# HT32F12364.net
KiCad netlist of a schematic drawn in Altium Designer
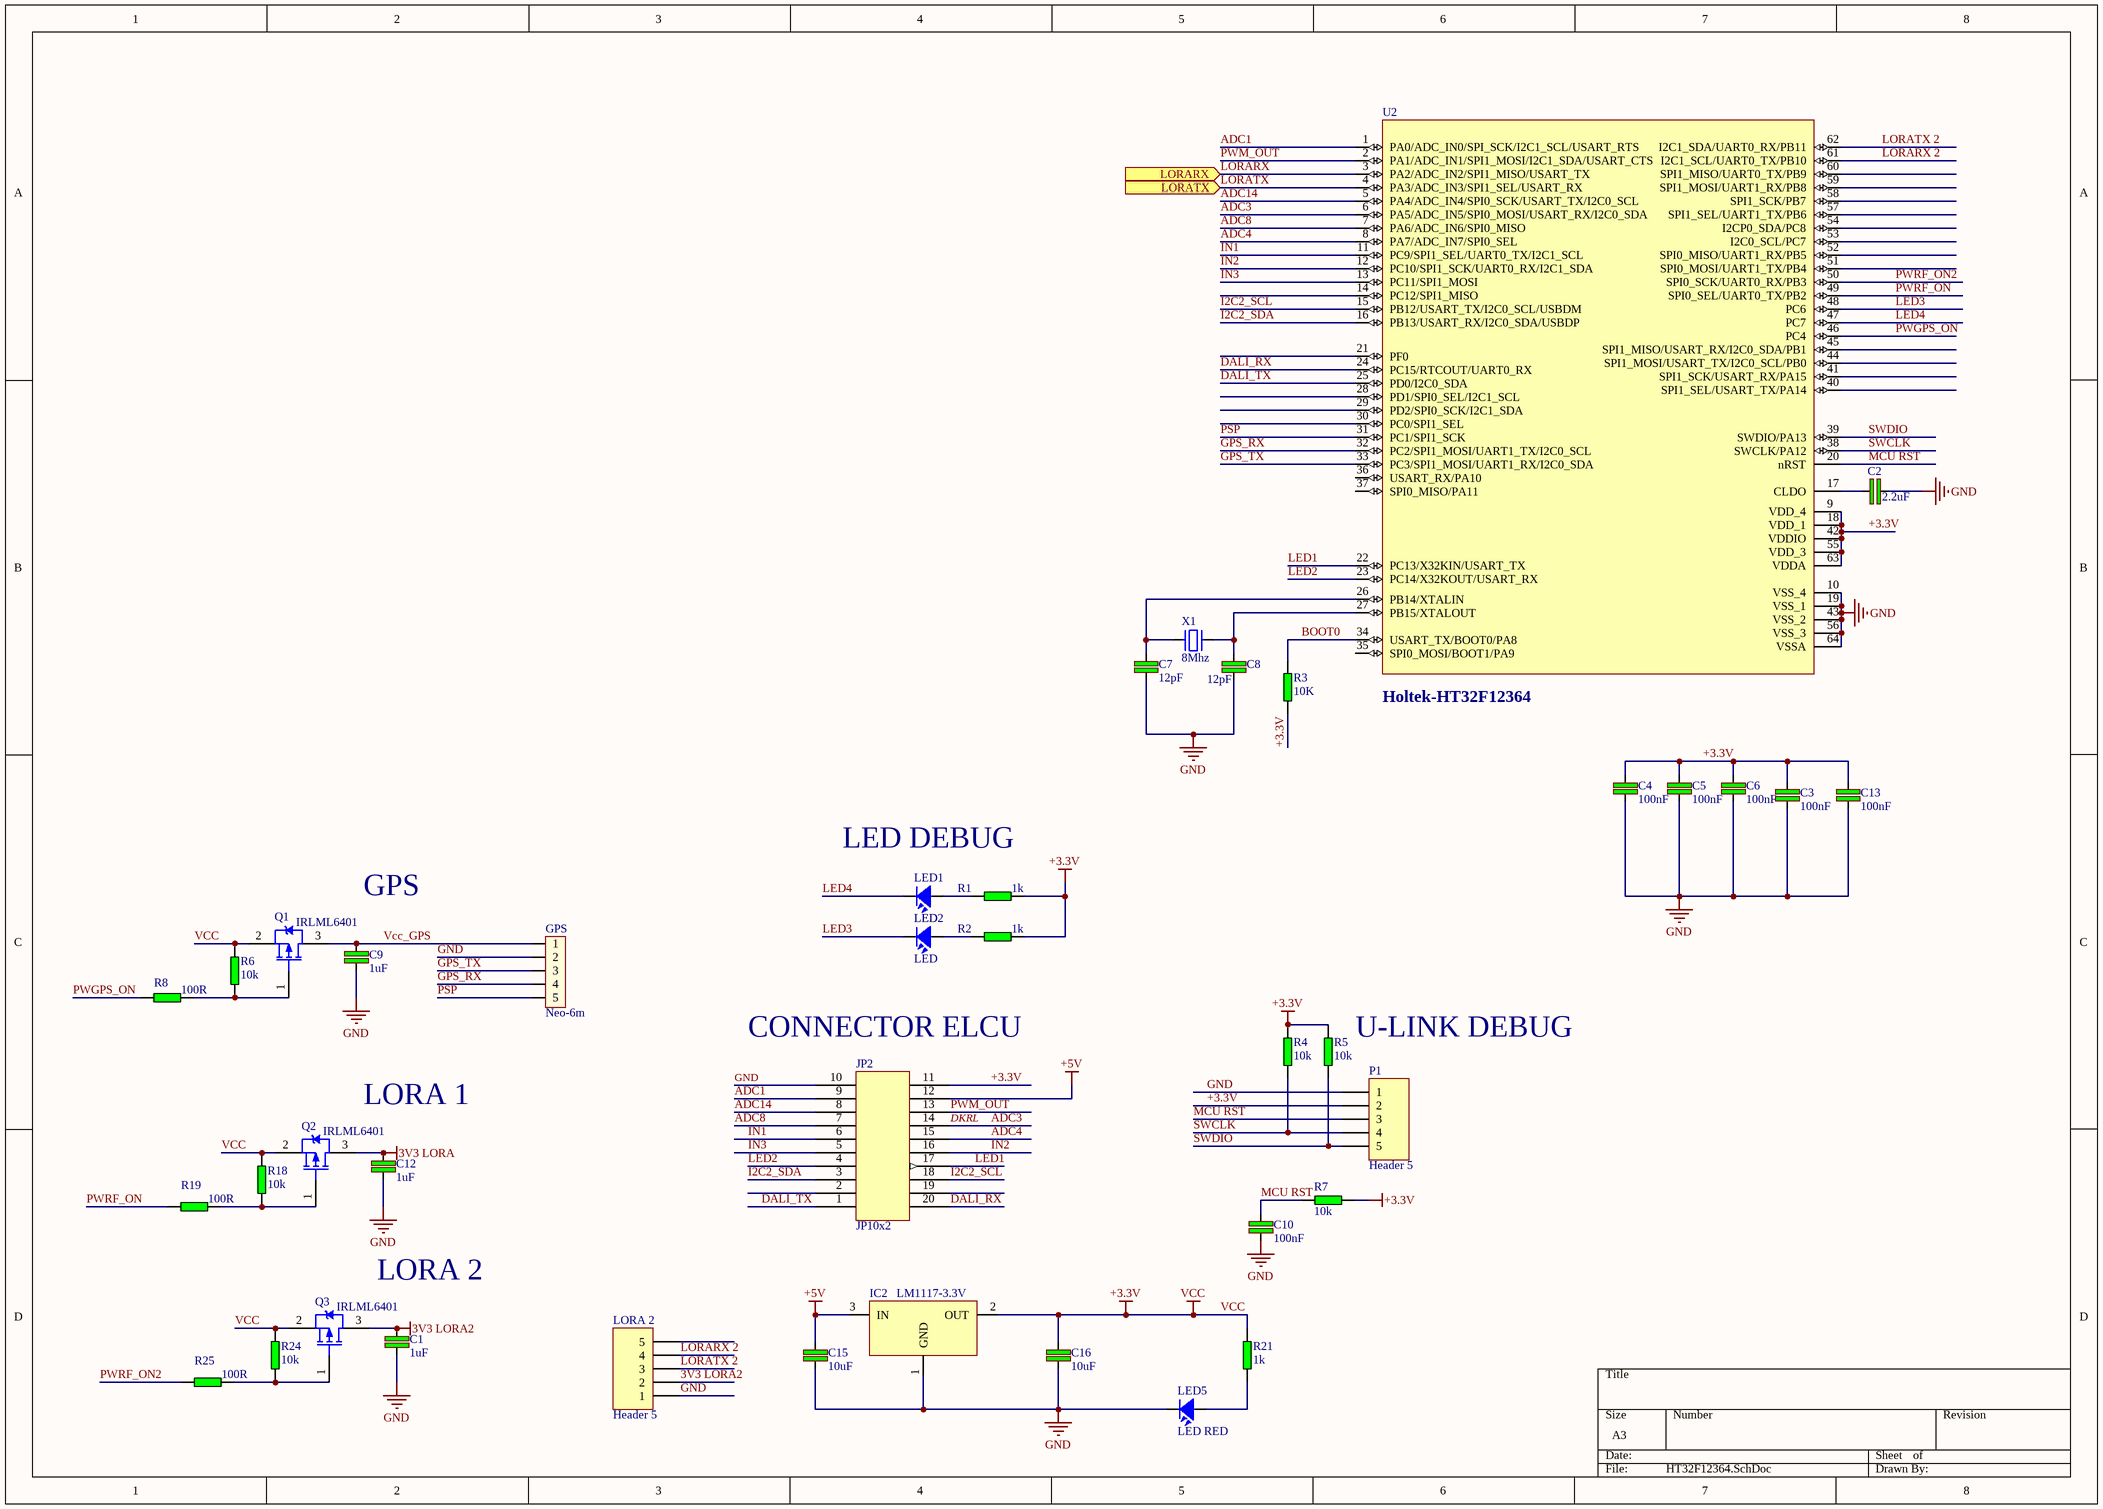
[diagram p0: HT32F12364.SchDoc]

(export (version "E")
  (design (tool "Eeschema 10.0.6"))
  (components
    (comp (ref "C1")
      (value "1uF")
      (footprint "C-0603")
      (description "Cap SMD")
      (libsource (lib "") (part "C_1"))
    )
    (comp (ref "C2")
      (value "2.2uF")
      (footprint "C-0603")
      (description "Cap SMD")
      (libsource (lib "") (part "C_2"))
    )
    (comp (ref "C3")
      (value "100nF")
      (footprint "C-0603")
      (description "Cap SMD")
      (libsource (lib "") (part "C_1"))
    )
    (comp (ref "C4")
      (value "100nF")
      (footprint "C-0603")
      (description "Cap SMD")
      (libsource (lib "") (part "C_1"))
    )
    (comp (ref "C5")
      (value "100nF")
      (footprint "C-0603")
      (description "Cap SMD")
      (libsource (lib "") (part "C_1"))
    )
    (comp (ref "C6")
      (value "100nF")
      (footprint "C-0603")
      (description "Cap SMD")
      (libsource (lib "") (part "C_1"))
    )
    (comp (ref "C7")
      (value "12pF")
      (footprint "C-0603")
      (description "Cap SMD")
      (libsource (lib "") (part "C_1"))
    )
    (comp (ref "C8")
      (value "12pF")
      (footprint "C-0603")
      (description "Cap SMD")
      (libsource (lib "") (part "C_1"))
    )
    (comp (ref "C9")
      (value "1uF")
      (footprint "C-0603")
      (description "Cap SMD")
      (libsource (lib "") (part "C_1"))
    )
    (comp (ref "C10")
      (value "100nF")
      (footprint "C-0603")
      (description "Cap SMD")
      (libsource (lib "Duy_Hai") (part "C"))
    )
    (comp (ref "C12")
      (value "1uF")
      (footprint "C-0603")
      (description "Cap SMD")
      (libsource (lib "") (part "C_1"))
    )
    (comp (ref "C13")
      (value "100nF")
      (footprint "C-0603")
      (description "Cap SMD")
      (libsource (lib "") (part "C_1"))
    )
    (comp (ref "C15")
      (value "10uF")
      (footprint "C-0805")
      (description "Cap np  1pF - 472pF")
      (libsource (lib "heromap") (part "CAP"))
    )
    (comp (ref "C16")
      (value "10uF")
      (footprint "C-0805")
      (description "Cap np  1pF - 472pF")
      (libsource (lib "heromap") (part "CAP"))
    )
    (comp (ref "GPS") (value "Neo-6m") (footprint "QUECTEL L80 MODULE") (libsource (lib "Cty1") (part "JP5")))
    (comp (ref "IC2")
      (value "LM1117-3.3V")
      (footprint "SOT223-4N")
      (fields (field (name "CREATOR") "Nguyen Ba Bien"))
      (libsource (lib "Cty1") (part "LM1117"))
    )
    (comp (ref "JP2")
      (value "JP10x2")
      (footprint "JP10-D2T")
      (description "Conector 10x2")
      (libsource (lib "Cty1") (part "CON10X2"))
    )
    (comp (ref "LED1")
      (value "LED")
      (footprint "LED-0805")
      (description "LED Single colour Green and Red")
      (libsource (lib "heromap") (part "LED"))
    )
    (comp (ref "LED2")
      (value "LED")
      (footprint "LED-0805")
      (description "LED Single colour Green and Red")
      (libsource (lib "heromap") (part "LED"))
    )
    (comp (ref "LED5")
      (value "LED RED")
      (footprint "LED-0805")
      (description "LED Single colour Green and Red")
      (libsource (lib "heromap") (part "LED"))
    )
    (comp (ref "LORA 2")
      (value "Header 5")
      (footprint "RAK3172 MODULE 2")
      (description "Header, 5-Pin")
      (fields (field (name "PUBLISHER") "Altium Limited"))
      (libsource (lib "heromap") (part "Header 5"))
    )
    (comp (ref "P1")
      (value "Header 5")
      (footprint "JP5")
      (description "Header, 5-Pin")
      (fields (field (name "PUBLISHER") "Altium Limited"))
      (libsource (lib "") (part "Header 5_1"))
    )
    (comp (ref "Q1")
      (value "IRLML6401")
      (footprint "Anh_Trung:SOT23")
      (description "HEXFET Power MOSFET")
      (fields (field (name "PUBLISHER") "Altium Limited"))
      (libsource (lib "IR Discrete MOSFET - Power") (part "IRLML6302"))
    )
    (comp (ref "Q2")
      (value "IRLML6401")
      (footprint "Anh_Trung:SOT23")
      (description "HEXFET Power MOSFET")
      (fields (field (name "PUBLISHER") "Altium Limited"))
      (libsource (lib "IR Discrete MOSFET - Power") (part "IRLML6302"))
    )
    (comp (ref "Q3")
      (value "IRLML6401")
      (footprint "Anh_Trung:SOT23")
      (description "HEXFET Power MOSFET")
      (fields (field (name "PUBLISHER") "Altium Limited"))
      (libsource (lib "IR Discrete MOSFET - Power") (part "IRLML6302"))
    )
    (comp (ref "R1")
      (value "1k")
      (footprint "R-0603")
      (description "Resistor 1/4W")
      (libsource (lib "") (part "RES_2"))
    )
    (comp (ref "R2")
      (value "1k")
      (footprint "R-0603")
      (description "Resistor 1/4W")
      (libsource (lib "") (part "RES_2"))
    )
    (comp (ref "R3")
      (value "10K")
      (footprint "R-0603")
      (description "Resistor 1/4W")
      (libsource (lib "Duy_Hai") (part "RES"))
    )
    (comp (ref "R4")
      (value "10k")
      (footprint "R-0603")
      (description "Resistor 1/4W")
      (libsource (lib "") (part "RES_1"))
    )
    (comp (ref "R5")
      (value "10k")
      (footprint "R-0603")
      (description "Resistor 1/4W")
      (libsource (lib "") (part "RES_1"))
    )
    (comp (ref "R6")
      (value "10k")
      (footprint "R-0603")
      (description "Resistor 1/4W")
      (libsource (lib "Duy_Hai") (part "RES"))
    )
    (comp (ref "R7")
      (value "10k")
      (footprint "R-0603")
      (description "Resistor 1/4W")
      (libsource (lib "") (part "RES_2"))
    )
    (comp (ref "R8")
      (value "100R")
      (footprint "R-0603")
      (description "Resistor 1/4W")
      (libsource (lib "") (part "RES_2"))
    )
    (comp (ref "R18")
      (value "10k")
      (footprint "R-0603")
      (description "Resistor 1/4W")
      (libsource (lib "Duy_Hai") (part "RES"))
    )
    (comp (ref "R19")
      (value "100R")
      (footprint "R-0603")
      (description "Resistor 1/4W")
      (libsource (lib "") (part "RES_2"))
    )
    (comp (ref "R21")
      (value "1k")
      (footprint "R-0603")
      (description "Resistor 1/4W")
      (libsource (lib "Duy_Hai") (part "RES"))
    )
    (comp (ref "R24")
      (value "10k")
      (footprint "R-0603")
      (description "Resistor 1/4W")
      (libsource (lib "Duy_Hai") (part "RES"))
    )
    (comp (ref "R25")
      (value "100R")
      (footprint "R-0603")
      (description "Resistor 1/4W")
      (libsource (lib "") (part "RES_2"))
    )
    (comp (ref "U2")
      (value "Holtek-HT32F12364")
      (footprint "LQFP-64PIN-7mmx7mm")
      (description "http://admin.epi-tech.com.vn//files/20210803/20210803162044_HT32F12364.pdf")
      (libsource (lib "ESP-07S") (part "Holtek-HT32F12364"))
    )
    (comp (ref "X1")
      (value "8Mhz")
      (footprint "XT2 - DAN - 5032")
      (description "Crystal For all Crystal 2pin.")
      (libsource (lib "Duy_Hai") (part "XT2"))
    )
  )
  (nets
    (net (code "1") (name "+3.3V") (class "Default")
      (node (ref "C13") (pin "1") (pinfunction "1_1") (pintype "passive"))
      (node (ref "C16") (pin "2") (pinfunction "2_2") (pintype "passive"))
      (node (ref "C3") (pin "1") (pinfunction "1_1") (pintype "passive"))
      (node (ref "C4") (pin "1") (pinfunction "1_1") (pintype "passive"))
      (node (ref "C5") (pin "1") (pinfunction "1_1") (pintype "passive"))
      (node (ref "C6") (pin "1") (pinfunction "1_1") (pintype "passive"))
      (node (ref "IC2") (pin "2") (pinfunction "OUT_2") (pintype "passive"))
      (node (ref "JP2") (pin "11") (pinfunction "13_11") (pintype "passive"))
      (node (ref "P1") (pin "2") (pinfunction "2_2") (pintype "passive"))
      (node (ref "Q1") (pin "2") (pinfunction "S_2") (pintype "passive"))
      (node (ref "Q2") (pin "2") (pinfunction "S_2") (pintype "passive"))
      (node (ref "Q3") (pin "2") (pinfunction "S_2") (pintype "passive"))
      (node (ref "R1") (pin "2") (pinfunction "2_2") (pintype "passive"))
      (node (ref "R18") (pin "2") (pinfunction "2_2") (pintype "passive"))
      (node (ref "R2") (pin "2") (pinfunction "2_2") (pintype "passive"))
      (node (ref "R21") (pin "2") (pinfunction "2_2") (pintype "passive"))
      (node (ref "R24") (pin "2") (pinfunction "2_2") (pintype "passive"))
      (node (ref "R3") (pin "1") (pinfunction "1_1") (pintype "passive"))
      (node (ref "R4") (pin "1") (pinfunction "1_1") (pintype "passive"))
      (node (ref "R5") (pin "1") (pinfunction "1_1") (pintype "passive"))
      (node (ref "R6") (pin "2") (pinfunction "2_2") (pintype "passive"))
      (node (ref "R7") (pin "2") (pinfunction "2_2") (pintype "passive"))
      (node (ref "U2") (pin "18") (pinfunction "VDD_1_18") (pintype "power_in"))
      (node (ref "U2") (pin "42") (pinfunction "VDDIO_42") (pintype "power_in"))
      (node (ref "U2") (pin "55") (pinfunction "VDD_3_55") (pintype "power_in"))
      (node (ref "U2") (pin "63") (pinfunction "VDDA_63") (pintype "power_in"))
      (node (ref "U2") (pin "9") (pinfunction "VDD_4_9") (pintype "power_in"))
    )
    (net (code "2") (name "+5V") (class "Default")
      (node (ref "C15") (pin "2") (pinfunction "2_2") (pintype "passive"))
      (node (ref "IC2") (pin "3") (pinfunction "IN_3") (pintype "passive"))
      (node (ref "JP2") (pin "12") (pinfunction "14_12") (pintype "passive"))
    )
    (net (code "3") (name "/ADC1") (class "Default")
      (node (ref "JP2") (pin "9") (pintype "passive"))
      (node (ref "U2") (pin "1") (pinfunction "PA0/ADC_IN0/SPI_SCK/I2C1_SCL/USART_RTS_1") (pintype "bidirectional"))
    )
    (net (code "4") (name "/ADC3") (class "Default")
      (node (ref "JP2") (pin "14") (pinfunction "16_14") (pintype "passive"))
      (node (ref "U2") (pin "6") (pinfunction "PA5/ADC_IN5/SPI0_MOSI/USART_RX/I2C0_SDA_6") (pintype "bidirectional"))
    )
    (net (code "5") (name "/ADC4") (class "Default")
      (node (ref "JP2") (pin "15") (pinfunction "17_15") (pintype "passive"))
      (node (ref "U2") (pin "8") (pinfunction "PA7/ADC_IN7/SPI0_SEL_8") (pintype "bidirectional"))
    )
    (net (code "6") (name "/ADC8") (class "Default")
      (node (ref "JP2") (pin "7") (pintype "passive"))
      (node (ref "U2") (pin "7") (pinfunction "PA6/ADC_IN6/SPI0_MISO_7") (pintype "bidirectional"))
    )
    (net (code "7") (name "/ADC14") (class "Default")
      (node (ref "JP2") (pin "8") (pintype "passive"))
      (node (ref "U2") (pin "5") (pinfunction "PA4/ADC_IN4/SPI0_SCK/USART_TX/I2C0_SCL_5") (pintype "bidirectional"))
    )
    (net (code "8") (name "/BOOT0") (class "Default")
      (node (ref "R3") (pin "2") (pinfunction "2_2") (pintype "passive"))
      (node (ref "U2") (pin "34") (pinfunction "USART_TX/BOOT0/PA8_34") (pintype "bidirectional"))
    )
    (net (code "9") (name "/DALI_RX") (class "Default")
      (node (ref "JP2") (pin "20") (pinfunction "22_20") (pintype "passive"))
      (node (ref "U2") (pin "24") (pinfunction "PC15/RTCOUT/UART0_RX_24") (pintype "bidirectional"))
    )
    (net (code "10") (name "/DALI_TX") (class "Default")
      (node (ref "JP2") (pin "1") (pintype "passive"))
      (node (ref "U2") (pin "25") (pinfunction "PD0/I2C0_SDA_25") (pintype "bidirectional"))
    )
    (net (code "11") (name "/GPS_RX") (class "Default")
      (node (ref "GPS") (pin "4") (pinfunction "4_4") (pintype "passive"))
      (node (ref "U2") (pin "32") (pinfunction "PC2/SPI1_MOSI/UART1_TX/I2C0_SCL_32") (pintype "bidirectional"))
    )
    (net (code "12") (name "/GPS_TX") (class "Default")
      (node (ref "GPS") (pin "3") (pinfunction "3_3") (pintype "passive"))
      (node (ref "U2") (pin "33") (pinfunction "PC3/SPI1_MOSI/UART1_RX/I2C0_SDA_33") (pintype "bidirectional"))
    )
    (net (code "13") (name "/I2C2_SCL") (class "Default")
      (node (ref "JP2") (pin "18") (pinfunction "20_18") (pintype "passive"))
      (node (ref "U2") (pin "15") (pinfunction "PB12/USART_TX/I2C0_SCL/USBDM_15") (pintype "bidirectional"))
    )
    (net (code "14") (name "/I2C2_SDA") (class "Default")
      (node (ref "JP2") (pin "3") (pintype "passive"))
      (node (ref "U2") (pin "16") (pinfunction "PB13/USART_RX/I2C0_SDA/USBDP_16") (pintype "bidirectional"))
    )
    (net (code "15") (name "/IN1") (class "Default")
      (node (ref "JP2") (pin "6") (pintype "passive"))
      (node (ref "U2") (pin "11") (pinfunction "PC9/SPI1_SEL/UART0_TX/I2C1_SCL_11") (pintype "bidirectional"))
    )
    (net (code "16") (name "/IN2") (class "Default")
      (node (ref "JP2") (pin "16") (pinfunction "18_16") (pintype "passive"))
      (node (ref "U2") (pin "12") (pinfunction "PC10/SPI1_SCK/UART0_RX/I2C1_SDA_12") (pintype "bidirectional"))
    )
    (net (code "17") (name "/IN3") (class "Default")
      (node (ref "JP2") (pin "5") (pintype "passive"))
      (node (ref "U2") (pin "13") (pinfunction "PC11/SPI1_MOSI_13") (pintype "bidirectional"))
    )
    (net (code "18") (name "/LED1") (class "Default")
      (node (ref "JP2") (pin "17") (pinfunction "19_17") (pintype "output"))
      (node (ref "U2") (pin "22") (pinfunction "PC13/X32KIN/USART_TX_22") (pintype "bidirectional"))
    )
    (net (code "19") (name "/LED2") (class "Default")
      (node (ref "JP2") (pin "4") (pintype "passive"))
      (node (ref "U2") (pin "23") (pinfunction "PC14/X32KOUT/USART_RX_23") (pintype "bidirectional"))
    )
    (net (code "20") (name "/LED3") (class "Default")
      (node (ref "LED2") (pin "2") (pinfunction "2_2") (pintype "passive"))
      (node (ref "U2") (pin "48") (pinfunction "PC6_48") (pintype "bidirectional"))
    )
    (net (code "21") (name "/LED4") (class "Default")
      (node (ref "LED1") (pin "2") (pinfunction "2_2") (pintype "passive"))
      (node (ref "U2") (pin "47") (pinfunction "PC7_47") (pintype "bidirectional"))
    )
    (net (code "22") (name "/LORARX") (class "Default")
      (node (ref "U2") (pin "3") (pinfunction "PA2/ADC_IN2/SPI1_MISO/USART_TX_3") (pintype "bidirectional"))
    )
    (net (code "23") (name "/LORARX 2") (class "Default")
      (node (ref "LORA 2") (pin "4") (pinfunction "4_4") (pintype "passive"))
      (node (ref "U2") (pin "61") (pinfunction "I2C1_SCL/UART0_TX/PB10_61") (pintype "bidirectional"))
    )
    (net (code "24") (name "/LORATX") (class "Default")
      (node (ref "U2") (pin "4") (pinfunction "PA3/ADC_IN3/SPI1_SEL/USART_RX_4") (pintype "bidirectional"))
    )
    (net (code "25") (name "/LORATX 2") (class "Default")
      (node (ref "LORA 2") (pin "3") (pinfunction "3_3") (pintype "passive"))
      (node (ref "U2") (pin "62") (pinfunction "I2C1_SDA/UART0_RX/PB11_62") (pintype "bidirectional"))
    )
    (net (code "26") (name "/MCU RST") (class "Default")
      (node (ref "C10") (pin "1") (pinfunction "1_1") (pintype "passive"))
      (node (ref "P1") (pin "3") (pinfunction "3_3") (pintype "passive"))
      (node (ref "R7") (pin "1") (pinfunction "1_1") (pintype "passive"))
      (node (ref "U2") (pin "20") (pinfunction "nRST_20") (pintype "passive"))
    )
    (net (code "27") (name "/PSP") (class "Default")
      (node (ref "GPS") (pin "5") (pinfunction "5_5") (pintype "passive"))
      (node (ref "U2") (pin "31") (pinfunction "PC1/SPI1_SCK_31") (pintype "bidirectional"))
    )
    (net (code "28") (name "/PWGPS_ON") (class "Default")
      (node (ref "R8") (pin "1") (pinfunction "1_1") (pintype "passive"))
      (node (ref "U2") (pin "46") (pinfunction "PC4_46") (pintype "bidirectional"))
    )
    (net (code "29") (name "/PWM_OUT") (class "Default")
      (node (ref "JP2") (pin "13") (pinfunction "15_13") (pintype "passive"))
      (node (ref "U2") (pin "2") (pinfunction "PA1/ADC_IN1/SPI1_MOSI/I2C1_SDA/USART_CTS_2") (pintype "bidirectional"))
    )
    (net (code "30") (name "/PWRF_ON") (class "Default")
      (node (ref "R19") (pin "1") (pinfunction "1_1") (pintype "passive"))
      (node (ref "U2") (pin "49") (pinfunction "SPI0_SEL/UART0_TX/PB2_49") (pintype "bidirectional"))
    )
    (net (code "31") (name "/PWRF_ON2") (class "Default")
      (node (ref "R25") (pin "1") (pinfunction "1_1") (pintype "passive"))
      (node (ref "U2") (pin "50") (pinfunction "SPI0_SCK/UART0_RX/PB3_50") (pintype "bidirectional"))
    )
    (net (code "32") (name "/SWCLK") (class "Default")
      (node (ref "P1") (pin "4") (pinfunction "4_4") (pintype "passive"))
      (node (ref "R4") (pin "2") (pinfunction "2_2") (pintype "passive"))
      (node (ref "U2") (pin "38") (pinfunction "SWCLK/PA12_38") (pintype "bidirectional"))
    )
    (net (code "33") (name "/SWDIO") (class "Default")
      (node (ref "P1") (pin "5") (pinfunction "5_5") (pintype "passive"))
      (node (ref "R5") (pin "2") (pinfunction "2_2") (pintype "passive"))
      (node (ref "U2") (pin "39") (pinfunction "SWDIO/PA13_39") (pintype "bidirectional"))
    )
    (net (code "34") (name "/Vcc_GPS") (class "Default")
      (node (ref "C9") (pin "1") (pinfunction "1_1") (pintype "passive"))
      (node (ref "GPS") (pin "1") (pinfunction "1_1") (pintype "passive"))
      (node (ref "Q1") (pin "3") (pinfunction "D_3") (pintype "passive"))
    )
    (net (code "35") (name "3V3 LORA") (class "Default")
      (node (ref "C12") (pin "1") (pinfunction "1_1") (pintype "passive"))
      (node (ref "Q2") (pin "3") (pinfunction "D_3") (pintype "passive"))
    )
    (net (code "36") (name "3V3 LORA2") (class "Default")
      (node (ref "C1") (pin "1") (pinfunction "1_1") (pintype "passive"))
      (node (ref "LORA 2") (pin "2") (pinfunction "2_2") (pintype "passive"))
      (node (ref "Q3") (pin "3") (pinfunction "D_3") (pintype "passive"))
    )
    (net (code "37") (name "GND") (class "Default")
      (node (ref "C1") (pin "2") (pinfunction "2_2") (pintype "passive"))
      (node (ref "C10") (pin "2") (pinfunction "2_2") (pintype "passive"))
      (node (ref "C12") (pin "2") (pinfunction "2_2") (pintype "passive"))
      (node (ref "C13") (pin "2") (pinfunction "2_2") (pintype "passive"))
      (node (ref "C15") (pin "1") (pinfunction "1_1") (pintype "passive"))
      (node (ref "C16") (pin "1") (pinfunction "1_1") (pintype "passive"))
      (node (ref "C2") (pin "2") (pinfunction "2_2") (pintype "passive"))
      (node (ref "C3") (pin "2") (pinfunction "2_2") (pintype "passive"))
      (node (ref "C4") (pin "2") (pinfunction "2_2") (pintype "passive"))
      (node (ref "C5") (pin "2") (pinfunction "2_2") (pintype "passive"))
      (node (ref "C6") (pin "2") (pinfunction "2_2") (pintype "passive"))
      (node (ref "C7") (pin "2") (pinfunction "2_2") (pintype "passive"))
      (node (ref "C8") (pin "2") (pinfunction "2_2") (pintype "passive"))
      (node (ref "C9") (pin "2") (pinfunction "2_2") (pintype "passive"))
      (node (ref "GPS") (pin "2") (pinfunction "2_2") (pintype "passive"))
      (node (ref "IC2") (pin "1") (pinfunction "GND_1") (pintype "passive"))
      (node (ref "JP2") (pin "10") (pintype "passive"))
      (node (ref "LED5") (pin "2") (pinfunction "2_2") (pintype "passive"))
      (node (ref "LORA 2") (pin "1") (pinfunction "1_1") (pintype "passive"))
      (node (ref "P1") (pin "1") (pinfunction "1_1") (pintype "passive"))
      (node (ref "U2") (pin "10") (pinfunction "VSS_4_10") (pintype "power_in"))
      (node (ref "U2") (pin "19") (pinfunction "VSS_1_19") (pintype "power_in"))
      (node (ref "U2") (pin "43") (pinfunction "VSS_2_43") (pintype "power_in"))
      (node (ref "U2") (pin "56") (pinfunction "VSS_3_56") (pintype "power_in"))
      (node (ref "U2") (pin "64") (pinfunction "VSSA_64") (pintype "power_in"))
    )
    (net (code "38") (name "Net-(LED1-Pad1)") (class "Default")
      (node (ref "LED1") (pin "1") (pinfunction "1_1") (pintype "passive"))
      (node (ref "R1") (pin "1") (pinfunction "1_1") (pintype "passive"))
    )
    (net (code "39") (name "Net-(LED2-Pad1)") (class "Default")
      (node (ref "LED2") (pin "1") (pinfunction "1_1") (pintype "passive"))
      (node (ref "R2") (pin "1") (pinfunction "1_1") (pintype "passive"))
    )
    (net (code "40") (name "Net-(LED5-Pad1)") (class "Default")
      (node (ref "LED5") (pin "1") (pinfunction "1_1") (pintype "passive"))
      (node (ref "R21") (pin "1") (pinfunction "1_1") (pintype "passive"))
    )
    (net (code "41") (name "Net-(Q1-G)") (class "Default")
      (node (ref "Q1") (pin "1") (pinfunction "G_1") (pintype "passive"))
      (node (ref "R6") (pin "1") (pinfunction "1_1") (pintype "passive"))
      (node (ref "R8") (pin "2") (pinfunction "2_2") (pintype "passive"))
    )
    (net (code "42") (name "Net-(Q2-G)") (class "Default")
      (node (ref "Q2") (pin "1") (pinfunction "G_1") (pintype "passive"))
      (node (ref "R18") (pin "1") (pinfunction "1_1") (pintype "passive"))
      (node (ref "R19") (pin "2") (pinfunction "2_2") (pintype "passive"))
    )
    (net (code "43") (name "Net-(Q3-G)") (class "Default")
      (node (ref "Q3") (pin "1") (pinfunction "G_1") (pintype "passive"))
      (node (ref "R24") (pin "1") (pinfunction "1_1") (pintype "passive"))
      (node (ref "R25") (pin "2") (pinfunction "2_2") (pintype "passive"))
    )
    (net (code "44") (name "Net-(U2-CLDO)") (class "Default")
      (node (ref "C2") (pin "1") (pinfunction "1_1") (pintype "passive"))
      (node (ref "U2") (pin "17") (pinfunction "CLDO_17") (pintype "power_in"))
    )
    (net (code "45") (name "Net-(U2-PB14{slash}XTALIN)") (class "Default")
      (node (ref "C7") (pin "1") (pinfunction "1_1") (pintype "passive"))
      (node (ref "U2") (pin "26") (pinfunction "PB14/XTALIN_26") (pintype "bidirectional"))
      (node (ref "X1") (pin "1") (pinfunction "1_1") (pintype "passive"))
    )
    (net (code "46") (name "Net-(U2-PB15{slash}XTALOUT)") (class "Default")
      (node (ref "C8") (pin "1") (pinfunction "1_1") (pintype "passive"))
      (node (ref "U2") (pin "27") (pinfunction "PB15/XTALOUT_27") (pintype "bidirectional"))
      (node (ref "X1") (pin "2") (pinfunction "2_2") (pintype "passive"))
    )
    (net (code "47") (name "unconnected-(JP2-21-Pad19)") (class "Default")
      (node (ref "JP2") (pin "19") (pinfunction "21_19") (pintype "passive"))
    )
    (net (code "48") (name "unconnected-(JP2-Pad2)") (class "Default")
      (node (ref "JP2") (pin "2") (pintype "passive"))
    )
    (net (code "49") (name "unconnected-(LORA 2-Pad5)") (class "Default")
      (node (ref "LORA 2") (pin "5") (pinfunction "5_5") (pintype "passive"))
    )
    (net (code "50") (name "unconnected-(U2-I2C0_SCL{slash}PC7-Pad53)") (class "Default")
      (node (ref "U2") (pin "53") (pinfunction "I2C0_SCL/PC7_53") (pintype "bidirectional"))
    )
    (net (code "51") (name "unconnected-(U2-I2CP0_SDA{slash}PC8-Pad54)") (class "Default")
      (node (ref "U2") (pin "54") (pinfunction "I2CP0_SDA/PC8_54") (pintype "bidirectional"))
    )
    (net (code "52") (name "unconnected-(U2-PC0{slash}SPI1_SEL-Pad30)") (class "Default")
      (node (ref "U2") (pin "30") (pinfunction "PC0/SPI1_SEL_30") (pintype "bidirectional"))
    )
    (net (code "53") (name "unconnected-(U2-PC12{slash}SPI1_MISO-Pad14)") (class "Default")
      (node (ref "U2") (pin "14") (pinfunction "PC12/SPI1_MISO_14") (pintype "bidirectional"))
    )
    (net (code "54") (name "unconnected-(U2-PD1{slash}SPI0_SEL{slash}I2C1_SCL-Pad28)") (class "Default")
      (node (ref "U2") (pin "28") (pinfunction "PD1/SPI0_SEL/I2C1_SCL_28") (pintype "bidirectional"))
    )
    (net (code "55") (name "unconnected-(U2-PD2{slash}SPI0_SCK{slash}I2C1_SDA-Pad29)") (class "Default")
      (node (ref "U2") (pin "29") (pinfunction "PD2/SPI0_SCK/I2C1_SDA_29") (pintype "bidirectional"))
    )
    (net (code "56") (name "unconnected-(U2-PF0-Pad21)") (class "Default")
      (node (ref "U2") (pin "21") (pinfunction "PF0_21") (pintype "bidirectional"))
    )
    (net (code "57") (name "unconnected-(U2-SPI0_MISO{slash}PA11-Pad37)") (class "Default")
      (node (ref "U2") (pin "37") (pinfunction "SPI0_MISO/PA11_37") (pintype "bidirectional"))
    )
    (net (code "58") (name "unconnected-(U2-SPI0_MISO{slash}UART1_RX{slash}PB5-Pad52)") (class "Default")
      (node (ref "U2") (pin "52") (pinfunction "SPI0_MISO/UART1_RX/PB5_52") (pintype "bidirectional"))
    )
    (net (code "59") (name "unconnected-(U2-SPI0_MOSI{slash}BOOT1{slash}PA9-Pad35)") (class "Default")
      (node (ref "U2") (pin "35") (pinfunction "SPI0_MOSI/BOOT1/PA9_35") (pintype "bidirectional"))
    )
    (net (code "60") (name "unconnected-(U2-SPI0_MOSI{slash}UART1_TX{slash}PB4-Pad51)") (class "Default")
      (node (ref "U2") (pin "51") (pinfunction "SPI0_MOSI/UART1_TX/PB4_51") (pintype "bidirectional"))
    )
    (net (code "61") (name "unconnected-(U2-SPI1_MISO{slash}UART0_TX{slash}PB9-Pad60)") (class "Default")
      (node (ref "U2") (pin "60") (pinfunction "SPI1_MISO/UART0_TX/PB9_60") (pintype "bidirectional"))
    )
    (net (code "62") (name "unconnected-(U2-SPI1_MISO{slash}USART_RX{slash}I2C0_SDA{slash}PB1-Pad45)") (class "Default")
      (node (ref "U2") (pin "45") (pinfunction "SPI1_MISO/USART_RX/I2C0_SDA/PB1_45") (pintype "bidirectional"))
    )
    (net (code "63") (name "unconnected-(U2-SPI1_MOSI{slash}UART1_RX{slash}PB8-Pad59)") (class "Default")
      (node (ref "U2") (pin "59") (pinfunction "SPI1_MOSI/UART1_RX/PB8_59") (pintype "bidirectional"))
    )
    (net (code "64") (name "unconnected-(U2-SPI1_MOSI{slash}USART_TX{slash}I2C0_SCL{slash}PB0-Pad44)") (class "Default")
      (node (ref "U2") (pin "44") (pinfunction "SPI1_MOSI/USART_TX/I2C0_SCL/PB0_44") (pintype "bidirectional"))
    )
    (net (code "65") (name "unconnected-(U2-SPI1_SCK{slash}PB7-Pad58)") (class "Default")
      (node (ref "U2") (pin "58") (pinfunction "SPI1_SCK/PB7_58") (pintype "bidirectional"))
    )
    (net (code "66") (name "unconnected-(U2-SPI1_SCK{slash}USART_RX{slash}PA15-Pad41)") (class "Default")
      (node (ref "U2") (pin "41") (pinfunction "SPI1_SCK/USART_RX/PA15_41") (pintype "bidirectional"))
    )
    (net (code "67") (name "unconnected-(U2-SPI1_SEL{slash}UART1_TX{slash}PB6-Pad57)") (class "Default")
      (node (ref "U2") (pin "57") (pinfunction "SPI1_SEL/UART1_TX/PB6_57") (pintype "bidirectional"))
    )
    (net (code "68") (name "unconnected-(U2-SPI1_SEL{slash}USART_TX{slash}PA14-Pad40)") (class "Default")
      (node (ref "U2") (pin "40") (pinfunction "SPI1_SEL/USART_TX/PA14_40") (pintype "bidirectional"))
    )
    (net (code "69") (name "unconnected-(U2-USART_RX{slash}PA10-Pad36)") (class "Default")
      (node (ref "U2") (pin "36") (pinfunction "USART_RX/PA10_36") (pintype "bidirectional"))
    )
  )
)
